# Main.net
KiCad netlist of a schematic drawn in Altium Designer
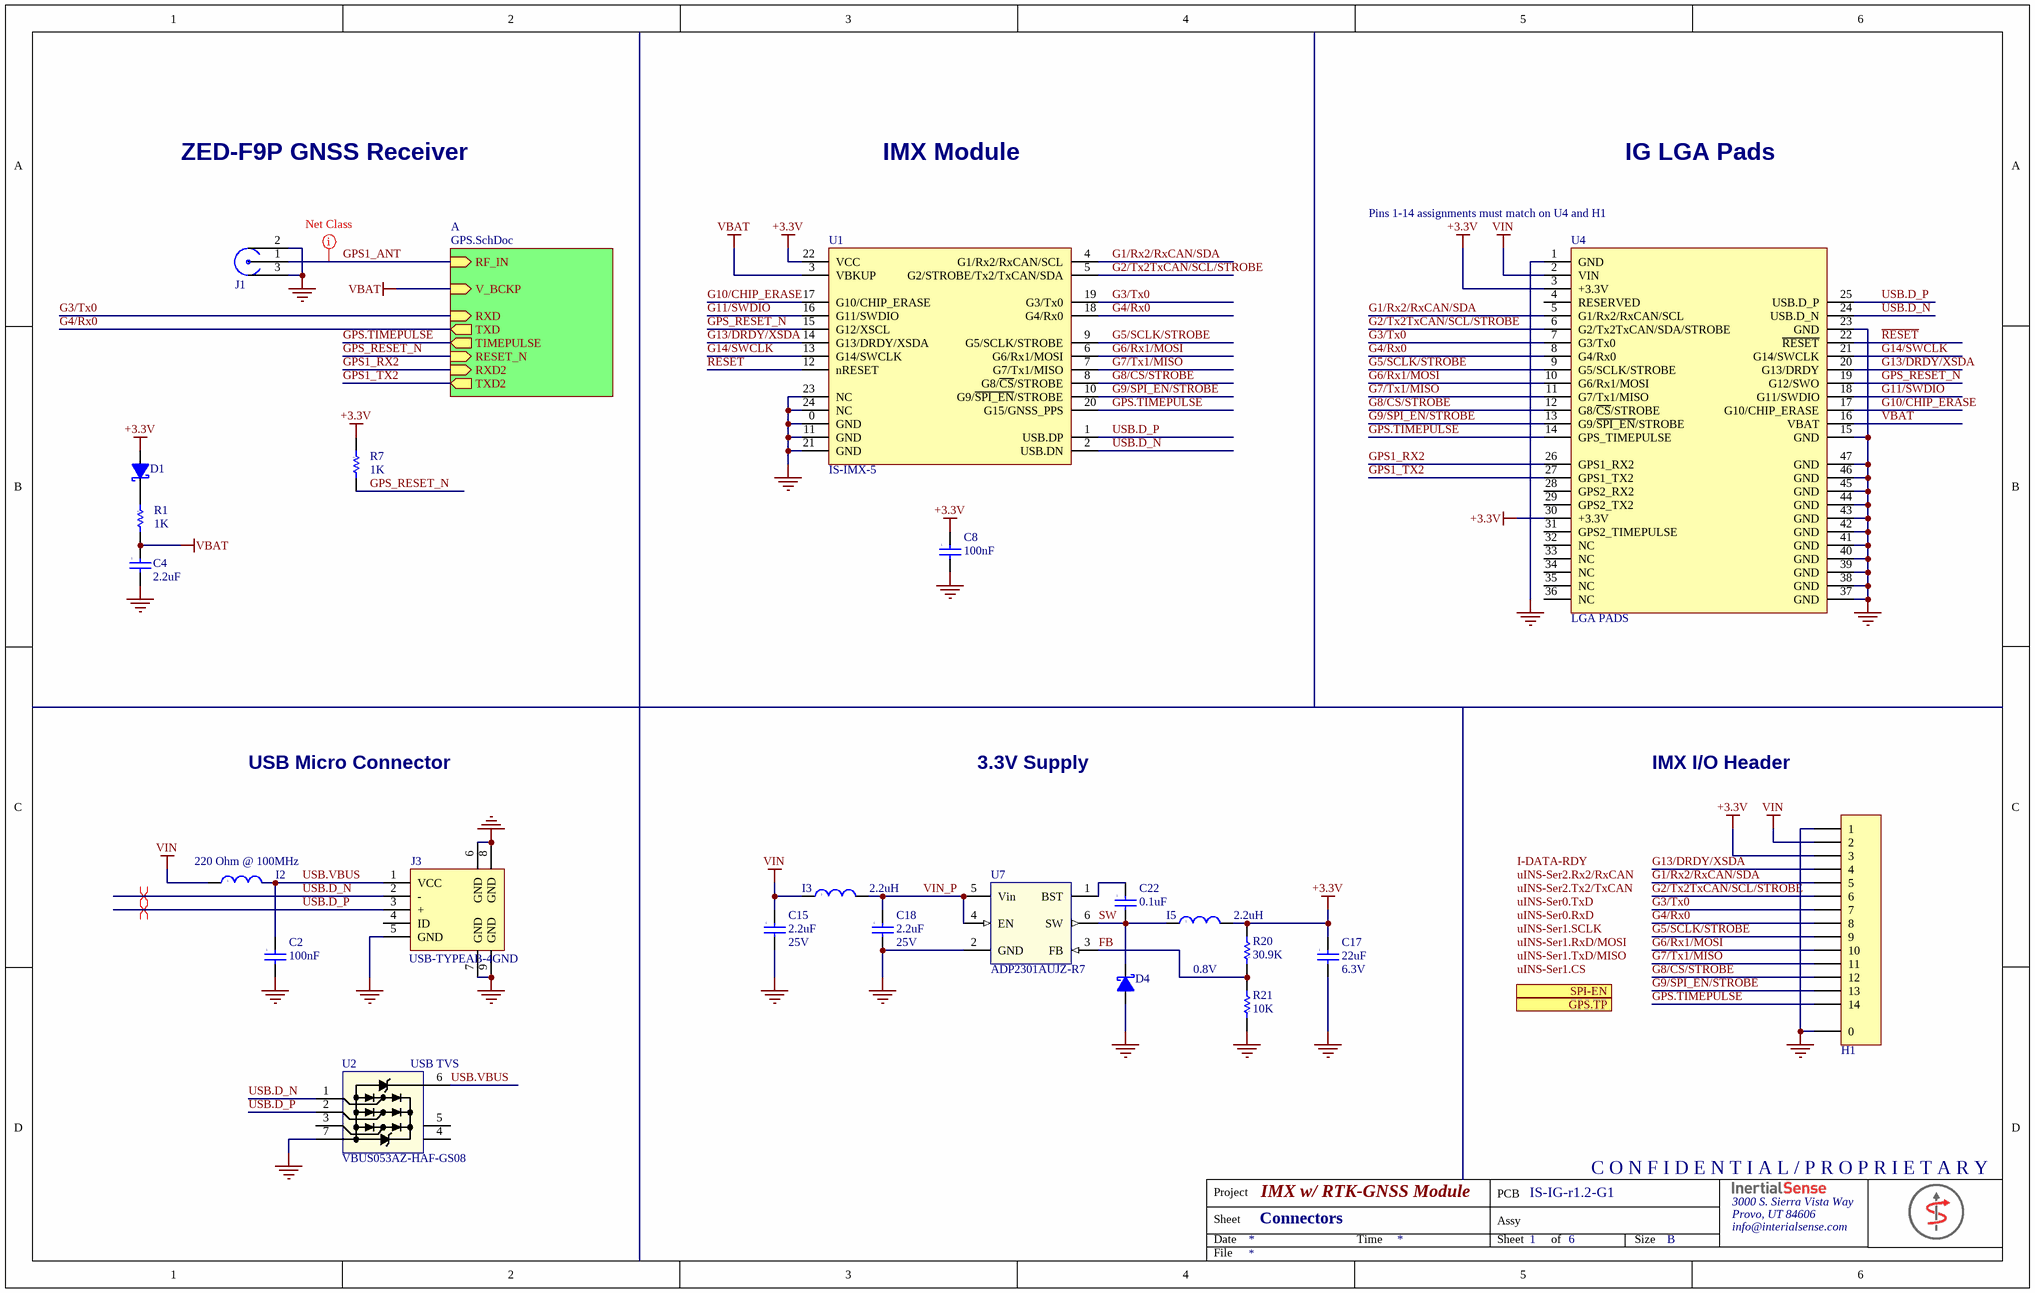
[diagram p0: Main.SchDoc]

(export (version "E")
  (design (tool "Eeschema 10.0.6"))
  (components
    (comp (ref "C2")
      (value "100nF")
      (footprint "0402")
      (description "CAP CER .10UF 50V X7R 10% 0402")
      (fields
        (field (name "MANUFACTURER") "TDK Corporation")
        (field (name "MANUFACTURER PART NUMBER") "C1005X7R1H104K")
        (field (name "PUBLISHER") "Altium Limited")
      )
      (libsource (lib "") (part "Cap_1"))
    )
    (comp (ref "C4")
      (value "2.2uF")
      (footprint "0402")
      (description "0402 2.2 uF 6.3 V ±10% Tolerance X6S Multilayer Ceramic Capacitor")
      (fields
        (field (name "MANUFACTURER") "Murata")
        (field (name "MANUFACTURER PART NUMBER") "GRM155C80J225KE95D")
        (field (name "PUBLISHER") "Altium Limited")
      )
      (libsource (lib "General") (part "Cap"))
    )
    (comp (ref "C8")
      (value "100nF")
      (footprint "0402")
      (description "CAP CER .10UF 50V X7R 10% 0402")
      (fields
        (field (name "MANUFACTURER") "TDK Corporation")
        (field (name "MANUFACTURER PART NUMBER") "C1005X7R1H104K")
        (field (name "PUBLISHER") "Altium Limited")
      )
      (libsource (lib "") (part "Cap_1"))
    )
    (comp (ref "C15")
      (value "2.2uF")
      (footprint "0603")
      (description "CAP CER 2.2UF 25V X6S 0603")
      (fields
        (field (name "MANUFACTURER") "Murata")
        (field (name "MANUFACTURER PART NUMBER") "GRT188C81E225KE13D")
        (field (name "VOLTAGE RATING") "25V")
        (field (name "PUBLISHER") "Altium Limited")
      )
      (libsource (lib "General") (part "Cap"))
    )
    (comp (ref "C17")
      (value "22uF")
      (footprint "0603")
      (description "CAP CER 22UF 6.3V X6S 0603")
      (fields
        (field (name "MANUFACTURER") "Murata")
        (field (name "MANUFACTURER PART NUMBER") "GRM188C80J226ME15D")
        (field (name "VOLTAGE RATING") "6.3V")
        (field (name "PUBLISHER") "Altium Limited")
      )
      (libsource (lib "General") (part "Cap"))
    )
    (comp (ref "C18")
      (value "2.2uF")
      (footprint "0603")
      (description "CAP CER 2.2UF 25V X6S 0603")
      (fields
        (field (name "MANUFACTURER") "Murata")
        (field (name "MANUFACTURER PART NUMBER") "GRT188C81E225KE13D")
        (field (name "VOLTAGE RATING") "25V")
        (field (name "PUBLISHER") "Altium Limited")
      )
      (libsource (lib "General") (part "Cap"))
    )
    (comp (ref "C22")
      (value "0.1uF")
      (footprint "0402")
      (description "CAP CER 0.1UF 50V X7R 0402")
      (fields
        (field (name "MANUFACTURER") "TDK")
        (field (name "MANUFACTURER PART NUMBER") "CGA2B3X7R1H104K050BB")
        (field (name "PUBLISHER") "Altium Limited")
      )
      (libsource (lib "General") (part "Cap"))
    )
    (comp (ref "D1")
      (value "Diode - Schottky")
      (footprint "D0603B")
      (description "DIODE SCHOTTKY 30V 2A 0603")
      (fields
        (field (name "MANUFACTURER") "Vishay")
        (field (name "MANUFACTURER PART NUMBER") "VSKY20301608-G4-08")
      )
      (libsource (lib "General") (part "Diode - Schottky"))
    )
    (comp (ref "D4")
      (value "Diode - Schottky")
      (footprint "D0603B")
      (description "DIODE SCHOTTKY 30V 2A 0603")
      (fields
        (field (name "MANUFACTURER") "Vishay")
        (field (name "MANUFACTURER PART NUMBER") "VSKY20301608-G4-08")
      )
      (libsource (lib "General") (part "Diode - Schottky"))
    )
    (comp (ref "H1")
      (value "Hdr - 14pin - mount")
      (footprint "SM14B-GHS-TB(LF)(SN)")
      (description "Conn Shrouded Header HDR 14 POS 1.25mm Solder ST Top Entry SMD T/R")
      (fields
        (field (name "MANUFACTURER") "JST")
        (field (name "MANUFACTURER PART NUMBER") "SM14B-GHS-TB(LF)(SN)")
      )
      (libsource (lib "Connectors") (part "Hdr - 14pin - mount"))
    )
    (comp (ref "I2")
      (value "220 Ohm @ 100MHz")
      (footprint "I0603")
      (description "FERRITE CHIP 220 OHM 2500MA 0603")
      (fields
        (field (name "MANUFACTURER") "Murata Electronics North America")
        (field (name "MANUFACTURER PART NUMBER") "BLM18SG221TN1D")
      )
      (libsource (lib "") (part "Inductor_1"))
    )
    (comp (ref "I3")
      (value "2.2uH")
      (footprint "0806")
      (description "FIXED IND 2.2UH 1.2A 110 MOHM")
      (fields
        (field (name "MANUFACTURER") "TDK")
        (field (name "MANUFACTURER PART NUMBER") "MLP2016H2R2MT0S1")
      )
      (libsource (lib "General") (part "Inductor"))
    )
    (comp (ref "I5")
      (value "2.2uH")
      (footprint "0806")
      (description "FIXED IND 2.2UH 1.2A 110 MOHM")
      (fields
        (field (name "MANUFACTURER") "TDK")
        (field (name "MANUFACTURER PART NUMBER") "MLP2016H2R2MT0S1")
      )
      (libsource (lib "General") (part "Inductor"))
    )
    (comp (ref "J1")
      (value "RF - GND x 2")
      (footprint "RF UMC SMD")
      (description "CONN UMC RCPT STR 50 OHM SMD")
      (fields
        (field (name "MANUFACTURER") "Emerson Network Power Connectivity Johnson")
        (field (name "MANUFACTURER PART NUMBER") "128-0711-201")
      )
      (libsource (lib "Connectors") (part "RF - GND x 2"))
    )
    (comp (ref "J3")
      (value "USB-TYPEAB-4GND")
      (footprint "USB Micro AB R/A THR")
      (description "CONN USB AB 4POS")
      (fields
        (field (name "MANUFACTURER") "Amphenol FCI")
        (field (name "MANUFACTURER PART NUMBER") "10118194-0001LF")
      )
      (libsource (lib "Connectors") (part "USB-TYPEAB-4GND"))
    )
    (comp (ref "R1")
      (value "1K")
      (footprint "R0402")
      (description "1 kOhms ±1% 0.063W, 1/16W Chip Resistor 0402 (1005 Metric) Moisture Resistant Thick Film")
      (fields
        (field (name "MANUFACTURER") "Yageo")
        (field (name "MANUFACTURER PART NUMBER") "RC0402FR-071KL")
      )
      (libsource (lib "General") (part "Res"))
    )
    (comp (ref "R7")
      (value "1K")
      (footprint "R0402")
      (description "1 kOhms ±1% 0.063W, 1/16W Chip Resistor 0402 (1005 Metric) Moisture Resistant Thick Film")
      (fields
        (field (name "MANUFACTURER") "Yageo")
        (field (name "MANUFACTURER PART NUMBER") "RC0402FR-071KL")
      )
      (libsource (lib "General") (part "Res"))
    )
    (comp (ref "R20")
      (value "30.9K")
      (footprint "R0402")
      (description "RES TF 30.9K OHM 1% 1/16W 0402")
      (fields
        (field (name "MANUFACTURER") "Stackpole Electronics Inc")
        (field (name "MANUFACTURER PART NUMBER") "RMCF0402FT30K9")
      )
      (libsource (lib "") (part "Res_1"))
    )
    (comp (ref "R21")
      (value "10K")
      (footprint "R0402")
      (description "RES 10.0K OHM 1/16W 1% 0402 SMD")
      (fields
        (field (name "MANUFACTURER") "Yageo")
        (field (name "MANUFACTURER PART NUMBER") "RC0402FR-0710KL")
      )
      (libsource (lib "") (part "Res_1"))
    )
    (comp (ref "U1")
      (value "IMX")
      (footprint "IS-IMX-5.0")
      (description "Inertial Sense IMX")
      (fields
        (field (name "MANUFACTURER") "Inertial Sense")
        (field (name "MANUFACTURER PART NUMBER") "IS-IMX-5")
      )
      (libsource (lib "IS-IMX-5") (part "IS-IMX-5.0"))
    )
    (comp (ref "U2")
      (value "VBUS053")
      (footprint "QFN50P160X160X60-6N")
      (description "ESD SUPPRESS 5.5V 36W 3-Line USB")
      (fields
        (field (name "MANUFACTURER") "Vishay Semiconductors")
        (field (name "MANUFACTURER PART NUMBER") "VBUS053AZ-HAF-GS08")
      )
      (libsource (lib "ICs") (part "VBUS053"))
    )
    (comp (ref "U4")
      (value "LGA PADS")
      (footprint "IG-1.2-G1_LGA")
      (description "IMX multi-frequency RTK-GNSS Module")
      (libsource (lib "Sensors") (part "IG_1.2-G1_LGA"))
    )
    (comp (ref "U7")
      (value "ADP2301")
      (footprint "MO-178-AB")
      (description "IC BUCK ADJ 1.2A 6TSOT")
      (fields
        (field (name "MANUFACTURER") "Analog Devices Inc")
        (field (name "MANUFACTURER PART NUMBER") "ADP2301AUJZ-R7")
      )
      (libsource (lib "ICs") (part "ADP2301"))
    )
  )
  (nets
    (net (code "1") (name "+3.3V") (class "Default")
      (node (ref "C17") (pin "1") (pinfunction "1_1") (pintype "passive"))
      (node (ref "C8") (pin "1") (pinfunction "1_1") (pintype "passive"))
      (node (ref "D1") (pin "A") (pinfunction "A_A") (pintype "passive"))
      (node (ref "H1") (pin "3") (pinfunction "3_3") (pintype "passive"))
      (node (ref "I5") (pin "2") (pinfunction "2_2") (pintype "passive"))
      (node (ref "R20") (pin "2") (pinfunction "2_2") (pintype "passive"))
      (node (ref "R7") (pin "1") (pinfunction "1_1") (pintype "passive"))
      (node (ref "U1") (pin "22") (pinfunction "VCC_22") (pintype "power_in"))
      (node (ref "U4") (pin "3") (pinfunction "+3.3V_3") (pintype "passive"))
      (node (ref "U4") (pin "30") (pinfunction "+3.3V_30") (pintype "passive"))
    )
    (net (code "2") (name "/FB") (class "Default")
      (node (ref "R20") (pin "1") (pinfunction "1_1") (pintype "passive"))
      (node (ref "R21") (pin "2") (pinfunction "2_2") (pintype "passive"))
      (node (ref "U7") (pin "3") (pinfunction "FB_3") (pintype "input"))
    )
    (net (code "3") (name "/G1{slash}Rx2{slash}RxCAN{slash}SDA") (class "Default")
      (node (ref "H1") (pin "5") (pinfunction "5_5") (pintype "passive"))
      (node (ref "U1") (pin "4") (pinfunction "G1/Rx2/RxCAN/SCL_4") (pintype "passive"))
      (node (ref "U4") (pin "5") (pinfunction "G1/Rx2/RxCAN/SCL_5") (pintype "passive"))
    )
    (net (code "4") (name "/G2{slash}Tx2TxCAN{slash}SCL{slash}STROBE") (class "Default")
      (node (ref "H1") (pin "6") (pinfunction "6_6") (pintype "passive"))
      (node (ref "U1") (pin "5") (pinfunction "G2/STROBE/Tx2/TxCAN/SDA_5") (pintype "passive"))
      (node (ref "U4") (pin "6") (pinfunction "G2/Tx2TxCAN/SDA/STROBE_6") (pintype "passive"))
    )
    (net (code "5") (name "/G3{slash}Tx0") (class "Default")
      (node (ref "H1") (pin "7") (pinfunction "7_7") (pintype "passive"))
      (node (ref "U1") (pin "19") (pinfunction "G3/Tx0_19") (pintype "passive"))
      (node (ref "U4") (pin "7") (pinfunction "G3/Tx0_7") (pintype "passive"))
    )
    (net (code "6") (name "/G4{slash}Rx0") (class "Default")
      (node (ref "H1") (pin "8") (pinfunction "8_8") (pintype "passive"))
      (node (ref "U1") (pin "18") (pinfunction "G4/Rx0_18") (pintype "passive"))
      (node (ref "U4") (pin "8") (pinfunction "G4/Rx0_8") (pintype "passive"))
    )
    (net (code "7") (name "/G5{slash}SCLK{slash}STROBE") (class "Default")
      (node (ref "H1") (pin "9") (pinfunction "9_9") (pintype "passive"))
      (node (ref "U1") (pin "9") (pinfunction "G5/SCLK/STROBE_9") (pintype "passive"))
      (node (ref "U4") (pin "9") (pinfunction "G5/SCLK/STROBE_9") (pintype "passive"))
    )
    (net (code "8") (name "/G6{slash}Rx1{slash}MOSI") (class "Default")
      (node (ref "H1") (pin "10") (pinfunction "10_10") (pintype "passive"))
      (node (ref "U1") (pin "6") (pinfunction "G6/Rx1/MOSI_6") (pintype "passive"))
      (node (ref "U4") (pin "10") (pinfunction "G6/Rx1/MOSI_10") (pintype "passive"))
    )
    (net (code "9") (name "/G7{slash}Tx1{slash}MISO") (class "Default")
      (node (ref "H1") (pin "11") (pinfunction "11_11") (pintype "passive"))
      (node (ref "U1") (pin "7") (pinfunction "G7/Tx1/MISO_7") (pintype "passive"))
      (node (ref "U4") (pin "11") (pinfunction "G7/Tx1/MISO_11") (pintype "passive"))
    )
    (net (code "10") (name "/G8{slash}~{CS}{slash}STROBE") (class "Default")
      (node (ref "H1") (pin "12") (pinfunction "12_12") (pintype "passive"))
      (node (ref "U1") (pin "8") (pinfunction "G8/~{CS}/STROBE_8") (pintype "passive"))
      (node (ref "U4") (pin "12") (pinfunction "G8/~{CS}/STROBE_12") (pintype "passive"))
    )
    (net (code "11") (name "/G9{slash}~{SPI_EN}{slash}STROBE") (class "Default")
      (node (ref "H1") (pin "13") (pinfunction "13_13") (pintype "passive"))
      (node (ref "U1") (pin "10") (pinfunction "G9/~{SPI_EN}/STROBE_10") (pintype "passive"))
      (node (ref "U4") (pin "13") (pinfunction "G9/~{SPI_EN}/STROBE_13") (pintype "passive"))
    )
    (net (code "12") (name "/G10{slash}CHIP_ERASE") (class "Default")
      (node (ref "U1") (pin "17") (pinfunction "G10/CHIP_ERASE_17") (pintype "passive"))
      (node (ref "U4") (pin "17") (pinfunction "G10/CHIP_ERASE_17") (pintype "passive"))
    )
    (net (code "13") (name "/G11{slash}SWDIO") (class "Default")
      (node (ref "U1") (pin "16") (pinfunction "G11/SWDIO_16") (pintype "passive"))
      (node (ref "U4") (pin "18") (pinfunction "G11/SWDIO_18") (pintype "passive"))
    )
    (net (code "14") (name "/G13{slash}DRDY{slash}XSDA") (class "Default")
      (node (ref "H1") (pin "4") (pinfunction "4_4") (pintype "passive"))
      (node (ref "U1") (pin "14") (pinfunction "G13/DRDY/XSDA_14") (pintype "passive"))
      (node (ref "U4") (pin "20") (pinfunction "G13/DRDY_20") (pintype "passive"))
    )
    (net (code "15") (name "/G14{slash}SWCLK") (class "Default")
      (node (ref "U1") (pin "13") (pinfunction "G14/SWCLK_13") (pintype "passive"))
      (node (ref "U4") (pin "21") (pinfunction "G14/SWCLK_21") (pintype "passive"))
    )
    (net (code "16") (name "/GPS.TIMEPULSE") (class "Default")
      (node (ref "H1") (pin "14") (pinfunction "14_14") (pintype "passive"))
      (node (ref "U1") (pin "20") (pinfunction "G15/GNSS_PPS_20") (pintype "passive"))
      (node (ref "U4") (pin "14") (pinfunction "GPS_TIMEPULSE_14") (pintype "passive"))
    )
    (net (code "18") (name "/GPS1_ANT") (class "Default")
      (node (ref "J1") (pin "1") (pinfunction "1_1") (pintype "passive"))
    )
    (net (code "19") (name "/GPS1_RX2") (class "Default")
      (node (ref "U4") (pin "26") (pinfunction "GPS1_RX2_26") (pintype "passive"))
    )
    (net (code "20") (name "/GPS1_TX2") (class "Default")
      (node (ref "U4") (pin "27") (pinfunction "GPS1_TX2_27") (pintype "passive"))
    )
    (net (code "21") (name "/GPS_RESET_N") (class "Default")
      (node (ref "R7") (pin "2") (pinfunction "2_2") (pintype "passive"))
      (node (ref "U1") (pin "15") (pinfunction "G12/XSCL_15") (pintype "passive"))
      (node (ref "U4") (pin "19") (pinfunction "G12/SWO_19") (pintype "passive"))
    )
    (net (code "23") (name "/RESET") (class "Default")
      (node (ref "U1") (pin "12") (pinfunction "nRESET_12") (pintype "passive"))
      (node (ref "U4") (pin "22") (pinfunction "~{RESET}_22") (pintype "passive"))
    )
    (net (code "25") (name "/SW") (class "Default")
      (node (ref "C22") (pin "2") (pinfunction "2_2") (pintype "passive"))
      (node (ref "D4") (pin "C") (pinfunction "C_C") (pintype "passive"))
      (node (ref "I5") (pin "1") (pinfunction "1_1") (pintype "passive"))
      (node (ref "U7") (pin "6") (pinfunction "SW_6") (pintype "output"))
    )
    (net (code "26") (name "/USB.D_N") (class "Default")
      (node (ref "J3") (pin "2") (pinfunction "-_2") (pintype "passive"))
      (node (ref "U1") (pin "2") (pinfunction "USB.DN_2") (pintype "passive"))
      (node (ref "U2") (pin "1") (pintype "passive"))
      (node (ref "U4") (pin "24") (pinfunction "USB.D_N_24") (pintype "passive"))
    )
    (net (code "27") (name "/USB.D_P") (class "Default")
      (node (ref "J3") (pin "3") (pinfunction "+_3") (pintype "passive"))
      (node (ref "U1") (pin "1") (pinfunction "USB.DP_1") (pintype "passive"))
      (node (ref "U2") (pin "2") (pintype "passive"))
      (node (ref "U4") (pin "25") (pinfunction "USB.D_P_25") (pintype "passive"))
    )
    (net (code "28") (name "/USB.VBUS") (class "Default")
      (node (ref "C2") (pin "1") (pinfunction "1_1") (pintype "passive"))
      (node (ref "I2") (pin "2") (pinfunction "2_2") (pintype "passive"))
      (node (ref "J3") (pin "1") (pinfunction "VCC_1") (pintype "passive"))
      (node (ref "U2") (pin "6") (pintype "passive"))
    )
    (net (code "29") (name "/VIN_P") (class "Default")
      (node (ref "C18") (pin "1") (pinfunction "1_1") (pintype "passive"))
      (node (ref "I3") (pin "2") (pinfunction "2_2") (pintype "passive"))
      (node (ref "U7") (pin "4") (pinfunction "EN_4") (pintype "input"))
      (node (ref "U7") (pin "5") (pinfunction "Vin_5") (pintype "power_in"))
    )
    (net (code "38") (name "GND") (class "Default")
      (node (ref "C15") (pin "2") (pinfunction "2_2") (pintype "passive"))
      (node (ref "C17") (pin "2") (pinfunction "2_2") (pintype "passive"))
      (node (ref "C18") (pin "2") (pinfunction "2_2") (pintype "passive"))
      (node (ref "C2") (pin "2") (pinfunction "2_2") (pintype "passive"))
      (node (ref "C4") (pin "2") (pinfunction "2_2") (pintype "passive"))
      (node (ref "C8") (pin "2") (pinfunction "2_2") (pintype "passive"))
      (node (ref "D4") (pin "A") (pinfunction "A_A") (pintype "passive"))
      (node (ref "H1") (pin "0") (pinfunction "0_0") (pintype "passive"))
      (node (ref "H1") (pin "1") (pinfunction "1_1") (pintype "passive"))
      (node (ref "J1") (pin "2") (pinfunction "2_2") (pintype "passive"))
      (node (ref "J1") (pin "3") (pinfunction "3_3") (pintype "passive"))
      (node (ref "J3") (pin "5") (pinfunction "GND_5") (pintype "passive"))
      (node (ref "J3") (pin "6") (pinfunction "GND_6") (pintype "passive"))
      (node (ref "J3") (pin "7") (pinfunction "GND_7") (pintype "passive"))
      (node (ref "J3") (pin "8") (pinfunction "GND_8") (pintype "passive"))
      (node (ref "J3") (pin "9") (pinfunction "GND_9") (pintype "passive"))
      (node (ref "R21") (pin "1") (pinfunction "1_1") (pintype "passive"))
      (node (ref "U1") (pin "0") (pinfunction "GND_0") (pintype "power_in"))
      (node (ref "U1") (pin "11") (pinfunction "GND_11") (pintype "power_in"))
      (node (ref "U1") (pin "21") (pinfunction "GND_21") (pintype "power_in"))
      (node (ref "U1") (pin "23") (pinfunction "NC_23") (pintype "power_in"))
      (node (ref "U1") (pin "24") (pinfunction "NC_24") (pintype "power_in"))
      (node (ref "U2") (pin "7") (pintype "passive"))
      (node (ref "U4") (pin "1") (pinfunction "GND_1") (pintype "passive"))
      (node (ref "U4") (pin "15") (pinfunction "GND_15") (pintype "passive"))
      (node (ref "U4") (pin "23") (pinfunction "GND_23") (pintype "passive"))
      (node (ref "U4") (pin "37") (pinfunction "GND_37") (pintype "passive"))
      (node (ref "U4") (pin "38") (pinfunction "GND_38") (pintype "passive"))
      (node (ref "U4") (pin "39") (pinfunction "GND_39") (pintype "passive"))
      (node (ref "U4") (pin "40") (pinfunction "GND_40") (pintype "passive"))
      (node (ref "U4") (pin "41") (pinfunction "GND_41") (pintype "passive"))
      (node (ref "U4") (pin "42") (pinfunction "GND_42") (pintype "passive"))
      (node (ref "U4") (pin "43") (pinfunction "GND_43") (pintype "passive"))
      (node (ref "U4") (pin "44") (pinfunction "GND_44") (pintype "passive"))
      (node (ref "U4") (pin "45") (pinfunction "GND_45") (pintype "passive"))
      (node (ref "U4") (pin "46") (pinfunction "GND_46") (pintype "passive"))
      (node (ref "U4") (pin "47") (pinfunction "GND_47") (pintype "passive"))
      (node (ref "U7") (pin "2") (pinfunction "GND_2") (pintype "power_in"))
    )
    (net (code "39") (name "Net-(D1-PadC)") (class "Default")
      (node (ref "D1") (pin "C") (pinfunction "C_C") (pintype "passive"))
      (node (ref "R1") (pin "1") (pinfunction "1_1") (pintype "passive"))
    )
    (net (code "40") (name "Net-(U7-BST)") (class "Default")
      (node (ref "C22") (pin "1") (pinfunction "1_1") (pintype "passive"))
      (node (ref "U7") (pin "1") (pinfunction "BST_1") (pintype "passive"))
    )
    (net (code "41") (name "VBAT") (class "Default")
      (node (ref "C4") (pin "1") (pinfunction "1_1") (pintype "passive"))
      (node (ref "R1") (pin "2") (pinfunction "2_2") (pintype "passive"))
      (node (ref "U1") (pin "3") (pinfunction "VBKUP_3") (pintype "passive"))
      (node (ref "U4") (pin "16") (pinfunction "VBAT_16") (pintype "passive"))
    )
    (net (code "42") (name "VIN") (class "Default")
      (node (ref "C15") (pin "1") (pinfunction "1_1") (pintype "passive"))
      (node (ref "H1") (pin "2") (pinfunction "2_2") (pintype "passive"))
      (node (ref "I2") (pin "1") (pinfunction "1_1") (pintype "passive"))
      (node (ref "I3") (pin "1") (pinfunction "1_1") (pintype "passive"))
      (node (ref "U4") (pin "2") (pinfunction "VIN_2") (pintype "passive"))
    )
    (net (code "43") (name "unconnected-(J3-ID-Pad4)") (class "Default")
      (node (ref "J3") (pin "4") (pinfunction "ID_4") (pintype "passive"))
    )
    (net (code "44") (name "unconnected-(U2-Pad3)") (class "Default")
      (node (ref "U2") (pin "3") (pintype "passive"))
    )
    (net (code "45") (name "unconnected-(U2-nc-Pad4)") (class "Default")
      (node (ref "U2") (pin "4") (pinfunction "nc_4") (pintype "passive"))
    )
    (net (code "46") (name "unconnected-(U2-nc-Pad5)") (class "Default")
      (node (ref "U2") (pin "5") (pinfunction "nc_5") (pintype "passive"))
    )
    (net (code "47") (name "unconnected-(U4-GPS2_RX2-Pad28)") (class "Default")
      (node (ref "U4") (pin "28") (pinfunction "GPS2_RX2_28") (pintype "passive"))
    )
    (net (code "48") (name "unconnected-(U4-GPS2_TIMEPULSE-Pad31)") (class "Default")
      (node (ref "U4") (pin "31") (pinfunction "GPS2_TIMEPULSE_31") (pintype "passive"))
    )
    (net (code "49") (name "unconnected-(U4-GPS2_TX2-Pad29)") (class "Default")
      (node (ref "U4") (pin "29") (pinfunction "GPS2_TX2_29") (pintype "passive"))
    )
    (net (code "50") (name "unconnected-(U4-NC-Pad32)") (class "Default")
      (node (ref "U4") (pin "32") (pinfunction "NC_32") (pintype "passive"))
    )
    (net (code "51") (name "unconnected-(U4-NC-Pad33)") (class "Default")
      (node (ref "U4") (pin "33") (pinfunction "NC_33") (pintype "passive"))
    )
    (net (code "52") (name "unconnected-(U4-NC-Pad34)") (class "Default")
      (node (ref "U4") (pin "34") (pinfunction "NC_34") (pintype "passive"))
    )
    (net (code "53") (name "unconnected-(U4-NC-Pad35)") (class "Default")
      (node (ref "U4") (pin "35") (pinfunction "NC_35") (pintype "passive"))
    )
    (net (code "54") (name "unconnected-(U4-NC-Pad36)") (class "Default")
      (node (ref "U4") (pin "36") (pinfunction "NC_36") (pintype "passive"))
    )
    (net (code "55") (name "unconnected-(U4-RESERVED-Pad4)") (class "Default")
      (node (ref "U4") (pin "4") (pinfunction "RESERVED_4") (pintype "passive"))
    )
  )
)
